# powersupply.net
KiCad netlist of a schematic drawn in EAGLE
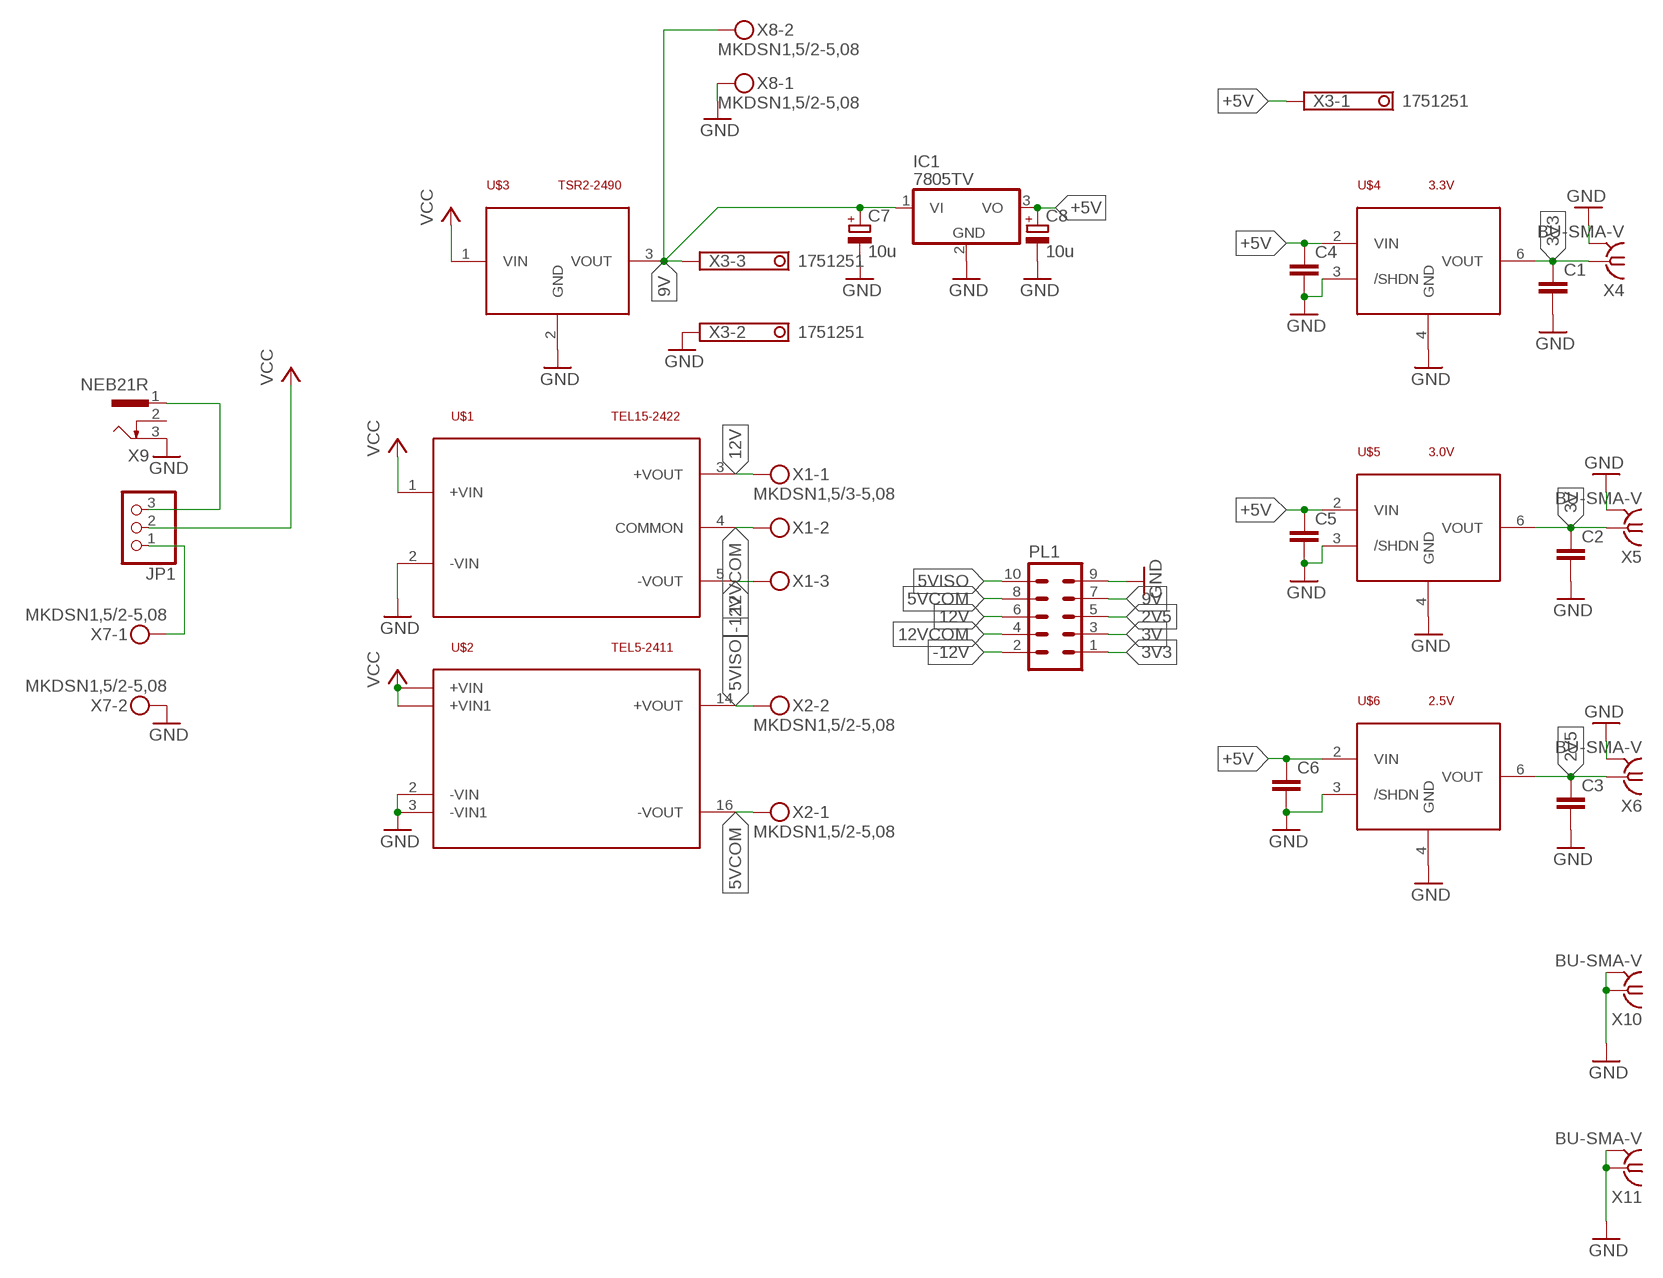
[diagram p0: schematic, sheet 1]

(export (version "E")
  (design (tool "Eeschema 10.0.6"))
  (components
    (comp (ref "C1")
      (value "C-EUC0805")
      (footprint "eagle-import:C0805")
      (libsource (lib "eagle-import") (part "C-EUC0805"))
    )
    (comp (ref "C2")
      (value "C-EUC0805")
      (footprint "eagle-import:C0805")
      (libsource (lib "eagle-import") (part "C-EUC0805"))
    )
    (comp (ref "C3")
      (value "C-EUC0805")
      (footprint "eagle-import:C0805")
      (libsource (lib "eagle-import") (part "C-EUC0805"))
    )
    (comp (ref "C4")
      (value "C-EUC0805")
      (footprint "eagle-import:C0805")
      (libsource (lib "eagle-import") (part "C-EUC0805"))
    )
    (comp (ref "C5")
      (value "C-EUC0805")
      (footprint "eagle-import:C0805")
      (libsource (lib "eagle-import") (part "C-EUC0805"))
    )
    (comp (ref "C6")
      (value "C-EUC0805")
      (footprint "eagle-import:C0805")
      (libsource (lib "eagle-import") (part "C-EUC0805"))
    )
    (comp (ref "C7")
      (value "10u")
      (footprint "eagle-import:PANASONIC_B")
      (libsource (lib "eagle-import") (part "CPOL-EUB"))
    )
    (comp (ref "C8")
      (value "10u")
      (footprint "eagle-import:PANASONIC_B")
      (libsource (lib "eagle-import") (part "CPOL-EUB"))
    )
    (comp (ref "IC1")
      (value "7805TV")
      (footprint "eagle-import:TO220V")
      (libsource (lib "eagle-import") (part "78TV05"))
    )
    (comp (ref "JP1")
      (value "PINHD-1X3")
      (footprint "eagle-import:1X03")
      (libsource (lib "eagle-import") (part "PINHD-1X3"))
    )
    (comp (ref "PL1")
      (value "10V")
      (footprint "eagle-import:10V")
      (libsource (lib "eagle-import") (part "10V"))
    )
    (comp (ref "U$1")
      (value "TEL15-2422")
      (footprint "eagle-import:TEL-15")
      (libsource (lib "eagle-import") (part "TEL-15"))
    )
    (comp (ref "U$2")
      (value "TEL5-2411")
      (footprint "eagle-import:TEL-5-SINGLE")
      (libsource (lib "eagle-import") (part "TEL-5-SINGLE"))
    )
    (comp (ref "U$3")
      (value "TSR2-2490")
      (footprint "eagle-import:TSR2")
      (libsource (lib "eagle-import") (part "TSR2"))
    )
    (comp (ref "U$4")
      (value "3.3V")
      (footprint "eagle-import:SO8")
      (libsource (lib "eagle-import") (part "LT1461"))
    )
    (comp (ref "U$5")
      (value "3.0V")
      (footprint "eagle-import:SO8")
      (libsource (lib "eagle-import") (part "LT1461"))
    )
    (comp (ref "U$6")
      (value "2.5V")
      (footprint "eagle-import:SO8")
      (libsource (lib "eagle-import") (part "LT1461"))
    )
    (comp (ref "X1")
      (value "MKDSN1,5/3-5,08")
      (footprint "eagle-import:MKDSN1,5_3-5,08")
      (libsource (lib "eagle-import") (part "MKDSN1,5/3-5,08"))
    )
    (comp (ref "X2")
      (value "MKDSN1,5/2-5,08")
      (footprint "eagle-import:MKDSN1,5_2-5,08")
      (libsource (lib "eagle-import") (part "MKDSN1,5/2-5,08"))
    )
    (comp (ref "X3")
      (value "1751251")
      (footprint "eagle-import:1751251")
      (libsource (lib "eagle-import") (part "1751251"))
    )
    (comp (ref "X4")
      (value "BU-SMA-V")
      (footprint "eagle-import:BU-SMA-V")
      (libsource (lib "eagle-import") (part "BU-SMA-V"))
    )
    (comp (ref "X5")
      (value "BU-SMA-V")
      (footprint "eagle-import:BU-SMA-V")
      (libsource (lib "eagle-import") (part "BU-SMA-V"))
    )
    (comp (ref "X6")
      (value "BU-SMA-V")
      (footprint "eagle-import:BU-SMA-V")
      (libsource (lib "eagle-import") (part "BU-SMA-V"))
    )
    (comp (ref "X7")
      (value "MKDSN1,5/2-5,08")
      (footprint "eagle-import:MKDSN1,5_2-5,08")
      (libsource (lib "eagle-import") (part "MKDSN1,5/2-5,08"))
    )
    (comp (ref "X8")
      (value "MKDSN1,5/2-5,08")
      (footprint "eagle-import:MKDSN1,5_2-5,08")
      (libsource (lib "eagle-import") (part "MKDSN1,5/2-5,08"))
    )
    (comp (ref "X9")
      (value "NEB21R")
      (footprint "eagle-import:NEB21R")
      (fields (field (name "MPN") "NEB 21 R"))
      (libsource (lib "eagle-import") (part "NEB21R"))
    )
    (comp (ref "X10")
      (value "BU-SMA-V")
      (footprint "eagle-import:BU-SMA-V")
      (libsource (lib "eagle-import") (part "BU-SMA-V"))
    )
    (comp (ref "X11")
      (value "BU-SMA-V")
      (footprint "eagle-import:BU-SMA-V")
      (libsource (lib "eagle-import") (part "BU-SMA-V"))
    )
  )
  (nets
    (net (code "1") (name "+5V") (class "Default")
      (node (ref "C4") (pin "1") (pinfunction "1_1") (pintype "passive"))
      (node (ref "C5") (pin "1") (pinfunction "1_1") (pintype "passive"))
      (node (ref "C6") (pin "1") (pinfunction "1_1") (pintype "passive"))
      (node (ref "C8") (pin "+") (pinfunction "+_+") (pintype "passive"))
      (node (ref "IC1") (pin "3") (pinfunction "VO_3") (pintype "passive"))
      (node (ref "U$4") (pin "2") (pinfunction "VIN_2") (pintype "power_in"))
      (node (ref "U$5") (pin "2") (pinfunction "VIN_2") (pintype "power_in"))
      (node (ref "U$6") (pin "2") (pinfunction "VIN_2") (pintype "power_in"))
      (node (ref "X3") (pin "1") (pinfunction "K_1") (pintype "passive"))
    )
    (net (code "2") (name "-12V") (class "Default")
      (node (ref "PL1") (pin "2") (pinfunction "2_2") (pintype "passive"))
      (node (ref "U$1") (pin "5") (pinfunction "-VOUT_5") (pintype "bidirectional"))
      (node (ref "X1") (pin "3") (pinfunction "KL_3") (pintype "passive"))
    )
    (net (code "3") (name "2V5") (class "Default")
      (node (ref "C3") (pin "1") (pinfunction "1_1") (pintype "passive"))
      (node (ref "PL1") (pin "5") (pinfunction "5_5") (pintype "passive"))
      (node (ref "U$6") (pin "6") (pinfunction "VOUT_6") (pintype "power_in"))
      (node (ref "X6") (pin "1") (pinfunction "1_1") (pintype "passive"))
    )
    (net (code "4") (name "3V") (class "Default")
      (node (ref "C2") (pin "1") (pinfunction "1_1") (pintype "passive"))
      (node (ref "PL1") (pin "3") (pinfunction "3_3") (pintype "passive"))
      (node (ref "U$5") (pin "6") (pinfunction "VOUT_6") (pintype "power_in"))
      (node (ref "X5") (pin "1") (pinfunction "1_1") (pintype "passive"))
    )
    (net (code "5") (name "3V3") (class "Default")
      (node (ref "C1") (pin "1") (pinfunction "1_1") (pintype "passive"))
      (node (ref "PL1") (pin "1") (pinfunction "1_1") (pintype "passive"))
      (node (ref "U$4") (pin "6") (pinfunction "VOUT_6") (pintype "power_in"))
      (node (ref "X4") (pin "1") (pinfunction "1_1") (pintype "passive"))
    )
    (net (code "6") (name "5VCOM") (class "Default")
      (node (ref "PL1") (pin "8") (pinfunction "8_8") (pintype "passive"))
      (node (ref "U$2") (pin "16") (pinfunction "-VOUT_16") (pintype "bidirectional"))
      (node (ref "X2") (pin "1") (pinfunction "KL_1") (pintype "passive"))
    )
    (net (code "7") (name "5VISO") (class "Default")
      (node (ref "PL1") (pin "10") (pinfunction "10_10") (pintype "passive"))
      (node (ref "U$2") (pin "14") (pinfunction "+VOUT_14") (pintype "bidirectional"))
      (node (ref "X2") (pin "2") (pinfunction "KL_2") (pintype "passive"))
    )
    (net (code "8") (name "9V") (class "Default")
      (node (ref "C7") (pin "+") (pinfunction "+_+") (pintype "passive"))
      (node (ref "IC1") (pin "1") (pinfunction "VI_1") (pintype "input"))
      (node (ref "PL1") (pin "7") (pinfunction "7_7") (pintype "passive"))
      (node (ref "U$3") (pin "3") (pinfunction "VOUT_3") (pintype "bidirectional"))
      (node (ref "X3") (pin "3") (pinfunction "K_3") (pintype "passive"))
      (node (ref "X8") (pin "2") (pinfunction "KL_2") (pintype "passive"))
    )
    (net (code "9") (name "12V") (class "Default")
      (node (ref "PL1") (pin "6") (pinfunction "6_6") (pintype "passive"))
      (node (ref "U$1") (pin "3") (pinfunction "+VOUT_3") (pintype "bidirectional"))
      (node (ref "X1") (pin "1") (pinfunction "KL_1") (pintype "passive"))
    )
    (net (code "10") (name "12VCOM") (class "Default")
      (node (ref "PL1") (pin "4") (pinfunction "4_4") (pintype "passive"))
      (node (ref "U$1") (pin "4") (pinfunction "COMMON_4") (pintype "bidirectional"))
      (node (ref "X1") (pin "2") (pinfunction "KL_2") (pintype "passive"))
    )
    (net (code "11") (name "GND") (class "Default")
      (node (ref "C1") (pin "2") (pinfunction "2_2") (pintype "passive"))
      (node (ref "C2") (pin "2") (pinfunction "2_2") (pintype "passive"))
      (node (ref "C3") (pin "2") (pinfunction "2_2") (pintype "passive"))
      (node (ref "C4") (pin "2") (pinfunction "2_2") (pintype "passive"))
      (node (ref "C5") (pin "2") (pinfunction "2_2") (pintype "passive"))
      (node (ref "C6") (pin "2") (pinfunction "2_2") (pintype "passive"))
      (node (ref "C7") (pin "-") (pinfunction "-_-") (pintype "passive"))
      (node (ref "C8") (pin "-") (pinfunction "-_-") (pintype "passive"))
      (node (ref "IC1") (pin "2") (pinfunction "GND_2") (pintype "passive"))
      (node (ref "PL1") (pin "9") (pinfunction "9_9") (pintype "passive"))
      (node (ref "U$1") (pin "2") (pinfunction "-VIN_2") (pintype "bidirectional"))
      (node (ref "U$2") (pin "2") (pinfunction "-VIN_2") (pintype "bidirectional"))
      (node (ref "U$2") (pin "3") (pinfunction "-VIN1_3") (pintype "bidirectional"))
      (node (ref "U$3") (pin "2") (pinfunction "GND_2") (pintype "bidirectional"))
      (node (ref "U$4") (pin "3") (pinfunction "/SHDN_3") (pintype "bidirectional"))
      (node (ref "U$4") (pin "4") (pinfunction "GND_4") (pintype "power_in"))
      (node (ref "U$5") (pin "3") (pinfunction "/SHDN_3") (pintype "bidirectional"))
      (node (ref "U$5") (pin "4") (pinfunction "GND_4") (pintype "power_in"))
      (node (ref "U$6") (pin "3") (pinfunction "/SHDN_3") (pintype "bidirectional"))
      (node (ref "U$6") (pin "4") (pinfunction "GND_4") (pintype "power_in"))
      (node (ref "X10") (pin "1") (pinfunction "1_1") (pintype "passive"))
      (node (ref "X10") (pin "2") (pinfunction "2_2") (pintype "passive"))
      (node (ref "X10") (pin "3") (pinfunction "2_3") (pintype "passive"))
      (node (ref "X10") (pin "4") (pinfunction "2_4") (pintype "passive"))
      (node (ref "X10") (pin "5") (pinfunction "2_5") (pintype "passive"))
      (node (ref "X11") (pin "1") (pinfunction "1_1") (pintype "passive"))
      (node (ref "X11") (pin "2") (pinfunction "2_2") (pintype "passive"))
      (node (ref "X11") (pin "3") (pinfunction "2_3") (pintype "passive"))
      (node (ref "X11") (pin "4") (pinfunction "2_4") (pintype "passive"))
      (node (ref "X11") (pin "5") (pinfunction "2_5") (pintype "passive"))
      (node (ref "X3") (pin "2") (pinfunction "K_2") (pintype "passive"))
      (node (ref "X4") (pin "2") (pinfunction "2_2") (pintype "passive"))
      (node (ref "X4") (pin "3") (pinfunction "2_3") (pintype "passive"))
      (node (ref "X4") (pin "4") (pinfunction "2_4") (pintype "passive"))
      (node (ref "X4") (pin "5") (pinfunction "2_5") (pintype "passive"))
      (node (ref "X5") (pin "2") (pinfunction "2_2") (pintype "passive"))
      (node (ref "X5") (pin "3") (pinfunction "2_3") (pintype "passive"))
      (node (ref "X5") (pin "4") (pinfunction "2_4") (pintype "passive"))
      (node (ref "X5") (pin "5") (pinfunction "2_5") (pintype "passive"))
      (node (ref "X6") (pin "2") (pinfunction "2_2") (pintype "passive"))
      (node (ref "X6") (pin "3") (pinfunction "2_3") (pintype "passive"))
      (node (ref "X6") (pin "4") (pinfunction "2_4") (pintype "passive"))
      (node (ref "X6") (pin "5") (pinfunction "2_5") (pintype "passive"))
      (node (ref "X7") (pin "2") (pinfunction "KL_2") (pintype "passive"))
      (node (ref "X8") (pin "1") (pinfunction "KL_1") (pintype "passive"))
      (node (ref "X9") (pin "3") (pinfunction "3_3") (pintype "passive"))
    )
    (net (code "12") (name "Net-(JP1-Pad3)") (class "Default")
      (node (ref "JP1") (pin "3") (pinfunction "3_3") (pintype "passive"))
      (node (ref "X9") (pin "1") (pinfunction "1_1") (pintype "passive"))
    )
    (net (code "13") (name "Net-(X7A-KL)") (class "Default")
      (node (ref "JP1") (pin "1") (pinfunction "1_1") (pintype "passive"))
      (node (ref "X7") (pin "1") (pinfunction "KL_1") (pintype "passive"))
    )
    (net (code "14") (name "VCC") (class "Default")
      (node (ref "JP1") (pin "2") (pinfunction "2_2") (pintype "passive"))
      (node (ref "U$1") (pin "1") (pinfunction "+VIN_1") (pintype "bidirectional"))
      (node (ref "U$2") (pin "22") (pinfunction "+VIN_22") (pintype "bidirectional"))
      (node (ref "U$2") (pin "23") (pinfunction "+VIN1_23") (pintype "bidirectional"))
      (node (ref "U$3") (pin "1") (pinfunction "VIN_1") (pintype "bidirectional"))
    )
    (net (code "15") (name "unconnected-(X9-Pad2)") (class "Default")
      (node (ref "X9") (pin "2") (pinfunction "2_2") (pintype "passive"))
    )
  )
)
